# x-IMU3-SA-GPS.net
KiCad netlist of a schematic drawn in Altium Designer
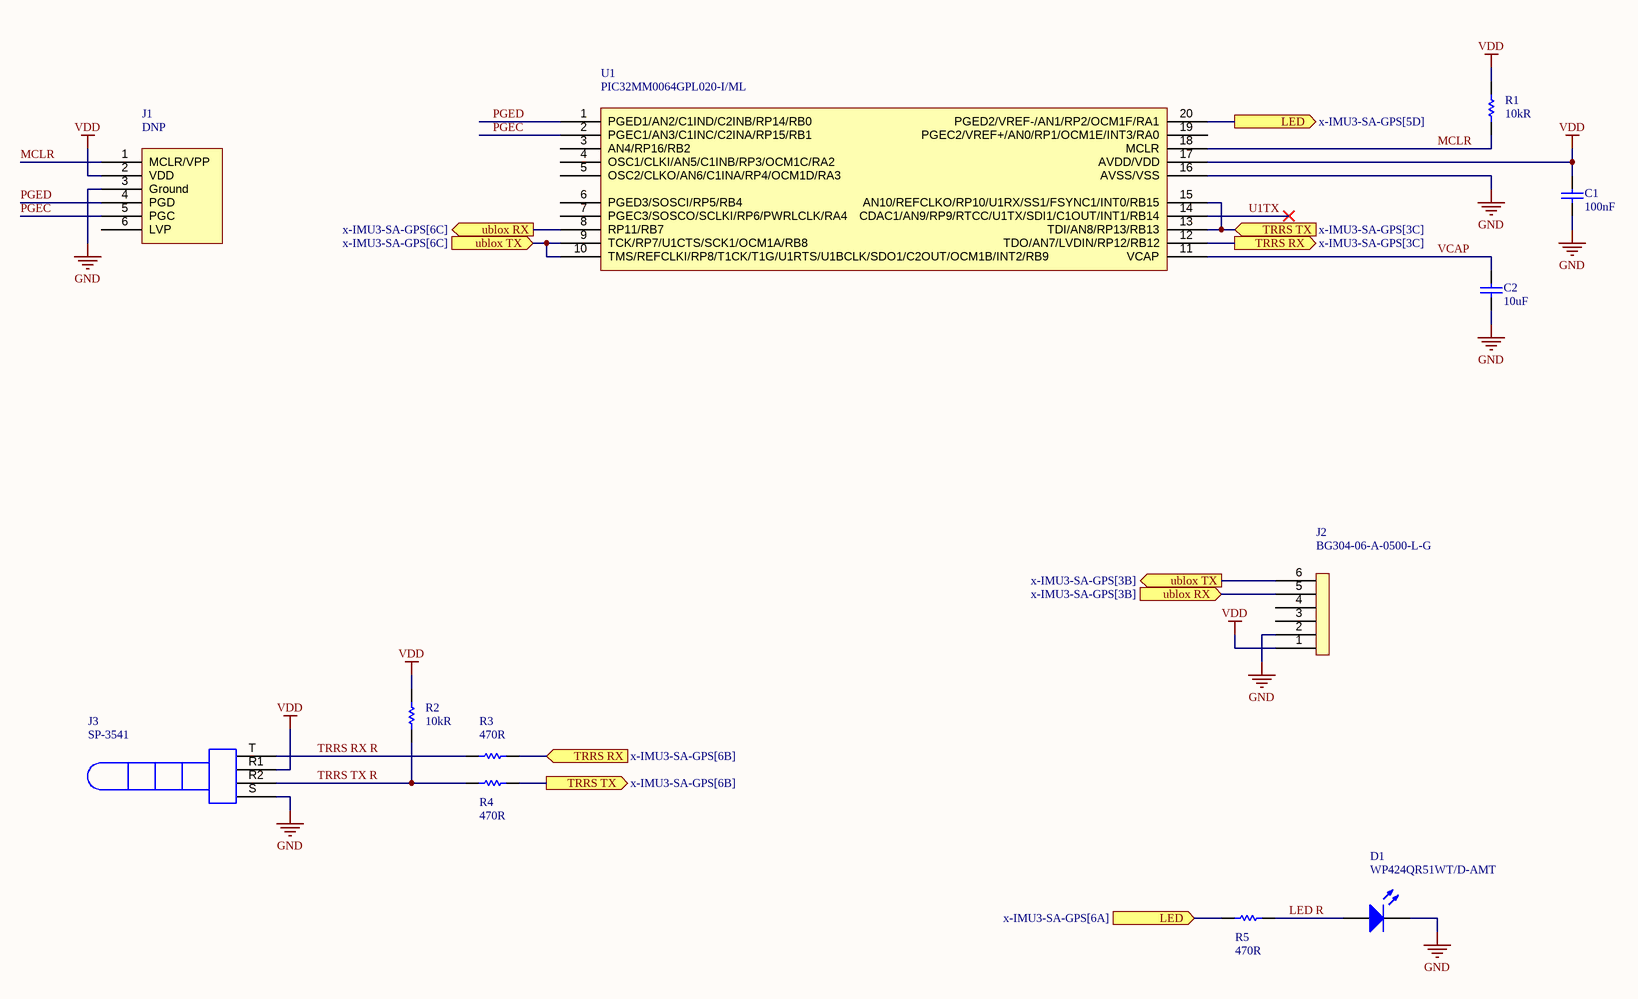
[diagram p0: x-IMU3-SA-GPS.SchDoc]

(export (version "E")
  (design (tool "Eeschema 10.0.6"))
  (components
    (comp (ref "C1") (value "100nF") (footprint "Capacitor 0402") (libsource (lib "x-io") (part "Capacitor")))
    (comp (ref "C2") (value "10uF") (footprint "Capacitor 0402") (libsource (lib "x-io") (part "Capacitor")))
    (comp (ref "D1") (value "WP424QR51WT/D-AMT") (footprint "LED 3mm") (libsource (lib "x-io") (part "LED")))
    (comp (ref "J1")
      (value "DNP")
      (footprint "Tag Connect No Legs")
      (libsource (lib "x-io") (part "MPLAB ICSP"))
    )
    (comp (ref "J2")
      (value "BG304-06-A-0500-L-G")
      (footprint "BG304-06-A-0500-L-G")
      (libsource (lib "x-io") (part "BG304-06-A-0500-L-G"))
    )
    (comp (ref "J3") (value "SP-3541") (footprint "SP-3541") (libsource (lib "x-io") (part "SP-3541")))
    (comp (ref "R1") (value "10kR") (footprint "Resistor 0402") (libsource (lib "x-io") (part "Resistor")))
    (comp (ref "R2") (value "10kR") (footprint "Resistor 0402") (libsource (lib "x-io") (part "Resistor")))
    (comp (ref "R3") (value "470R") (footprint "Resistor 0402") (libsource (lib "x-io") (part "Resistor")))
    (comp (ref "R4") (value "470R") (footprint "Resistor 0402") (libsource (lib "x-io") (part "Resistor")))
    (comp (ref "R5") (value "470R") (footprint "Resistor 0402") (libsource (lib "x-io") (part "Resistor")))
    (comp (ref "U1")
      (value "PIC32MM0064GPL020-I/ML")
      (footprint "QFN-20")
      (libsource (lib "x-io") (part "PIC32MM0064GPL020-I/ML"))
    )
  )
  (nets
    (net (code "1") (name "/LED") (class "Default")
      (node (ref "R5") (pin "2") (pinfunction "2_2") (pintype "passive"))
      (node (ref "U1") (pin "20") (pinfunction "PGED2/VREF-/AN1/RP2/OCM1F/RA1_20") (pintype "passive"))
    )
    (net (code "2") (name "/LED R") (class "Default")
      (node (ref "D1") (pin "A") (pinfunction "A_A") (pintype "passive"))
      (node (ref "R5") (pin "1") (pinfunction "1_1") (pintype "passive"))
    )
    (net (code "3") (name "/MCLR") (class "Default")
      (node (ref "J1") (pin "1") (pinfunction "MCLR/VPP_1") (pintype "passive"))
      (node (ref "R1") (pin "1") (pinfunction "1_1") (pintype "passive"))
      (node (ref "U1") (pin "18") (pinfunction "MCLR_18") (pintype "passive"))
    )
    (net (code "4") (name "/PGEC") (class "Default")
      (node (ref "J1") (pin "5") (pinfunction "PGC_5") (pintype "passive"))
      (node (ref "U1") (pin "2") (pinfunction "PGEC1/AN3/C1INC/C2INA/RP15/RB1_2") (pintype "passive"))
    )
    (net (code "5") (name "/PGED") (class "Default")
      (node (ref "J1") (pin "4") (pinfunction "PGD_4") (pintype "passive"))
      (node (ref "U1") (pin "1") (pinfunction "PGED1/AN2/C1IND/C2INB/RP14/RB0_1") (pintype "passive"))
    )
    (net (code "6") (name "/TRRS RX") (class "Default")
      (node (ref "R3") (pin "1") (pinfunction "1_1") (pintype "passive"))
      (node (ref "U1") (pin "12") (pinfunction "TDO/AN7/LVDIN/RP12/RB12_12") (pintype "passive"))
    )
    (net (code "7") (name "/TRRS RX R") (class "Default")
      (node (ref "J3") (pin "T") (pinfunction "T_T") (pintype "passive"))
      (node (ref "R3") (pin "2") (pinfunction "2_2") (pintype "passive"))
    )
    (net (code "8") (name "/TRRS TX") (class "Default")
      (node (ref "R4") (pin "1") (pinfunction "1_1") (pintype "passive"))
      (node (ref "U1") (pin "13") (pinfunction "TDI/AN8/RP13/RB13_13") (pintype "passive"))
      (node (ref "U1") (pin "15") (pinfunction "AN10/REFCLKO/RP10/U1RX/SS1/FSYNC1/INT0/RB15_15") (pintype "passive"))
    )
    (net (code "9") (name "/TRRS TX R") (class "Default")
      (node (ref "J3") (pin "R2") (pinfunction "R2_R2") (pintype "passive"))
      (node (ref "R2") (pin "1") (pinfunction "1_1") (pintype "passive"))
      (node (ref "R4") (pin "2") (pinfunction "2_2") (pintype "passive"))
    )
    (net (code "10") (name "/U1TX") (class "Default")
      (node (ref "U1") (pin "14") (pinfunction "CDAC1/AN9/RP9/RTCC/U1TX/SDI1/C1OUT/INT1/RB14_14") (pintype "passive+no_connect"))
    )
    (net (code "11") (name "/VCAP") (class "Default")
      (node (ref "C2") (pin "2") (pinfunction "2_2") (pintype "passive"))
      (node (ref "U1") (pin "11") (pinfunction "VCAP_11") (pintype "passive"))
    )
    (net (code "12") (name "/ublox RX") (class "Default")
      (node (ref "J2") (pin "5") (pinfunction "5_5") (pintype "passive"))
      (node (ref "U1") (pin "8") (pinfunction "RP11/RB7_8") (pintype "passive"))
    )
    (net (code "13") (name "/ublox TX") (class "Default")
      (node (ref "J2") (pin "6") (pinfunction "6_6") (pintype "passive"))
      (node (ref "U1") (pin "10") (pinfunction "TMS/REFCLKI/RP8/T1CK/T1G/U1RTS/U1BCLK/SDO1/C2OUT/OCM1B/INT2/RB9_10") (pintype "passive"))
      (node (ref "U1") (pin "9") (pinfunction "TCK/RP7/U1CTS/SCK1/OCM1A/RB8_9") (pintype "passive"))
    )
    (net (code "14") (name "GND") (class "Default")
      (node (ref "C1") (pin "1") (pinfunction "1_1") (pintype "passive"))
      (node (ref "C2") (pin "1") (pinfunction "1_1") (pintype "passive"))
      (node (ref "D1") (pin "K") (pinfunction "K_K") (pintype "passive"))
      (node (ref "J1") (pin "3") (pinfunction "Ground_3") (pintype "passive"))
      (node (ref "J2") (pin "2") (pinfunction "2_2") (pintype "passive"))
      (node (ref "J3") (pin "S") (pinfunction "S_S") (pintype "passive"))
      (node (ref "U1") (pin "16") (pinfunction "AVSS/VSS_16") (pintype "passive"))
    )
    (net (code "15") (name "VDD") (class "Default")
      (node (ref "C1") (pin "2") (pinfunction "2_2") (pintype "passive"))
      (node (ref "J1") (pin "2") (pinfunction "VDD_2") (pintype "passive"))
      (node (ref "J2") (pin "1") (pinfunction "1_1") (pintype "passive"))
      (node (ref "J3") (pin "R1") (pinfunction "R1_R1") (pintype "passive"))
      (node (ref "R1") (pin "2") (pinfunction "2_2") (pintype "passive"))
      (node (ref "R2") (pin "2") (pinfunction "2_2") (pintype "passive"))
      (node (ref "U1") (pin "17") (pinfunction "AVDD/VDD_17") (pintype "passive"))
    )
    (net (code "16") (name "unconnected-(J1-LVP-Pad6)") (class "Default")
      (node (ref "J1") (pin "6") (pinfunction "LVP_6") (pintype "passive"))
    )
    (net (code "17") (name "unconnected-(J2-Pad3)") (class "Default")
      (node (ref "J2") (pin "3") (pinfunction "3_3") (pintype "passive"))
    )
    (net (code "18") (name "unconnected-(J2-Pad4)") (class "Default")
      (node (ref "J2") (pin "4") (pinfunction "4_4") (pintype "passive"))
    )
    (net (code "19") (name "unconnected-(U1-AN4{slash}RP16{slash}RB2-Pad3)") (class "Default")
      (node (ref "U1") (pin "3") (pinfunction "AN4/RP16/RB2_3") (pintype "passive"))
    )
    (net (code "20") (name "unconnected-(U1-OSC1{slash}CLKI{slash}AN5{slash}C1INB{slash}RP3{slash}OCM1C{slash}RA2-Pad4)") (class "Default")
      (node (ref "U1") (pin "4") (pinfunction "OSC1/CLKI/AN5/C1INB/RP3/OCM1C/RA2_4") (pintype "passive"))
    )
    (net (code "21") (name "unconnected-(U1-OSC2{slash}CLKO{slash}AN6{slash}C1INA{slash}RP4{slash}OCM1D{slash}RA3-Pad5)") (class "Default")
      (node (ref "U1") (pin "5") (pinfunction "OSC2/CLKO/AN6/C1INA/RP4/OCM1D/RA3_5") (pintype "passive"))
    )
    (net (code "22") (name "unconnected-(U1-PGEC2{slash}VREF+{slash}AN0{slash}RP1{slash}OCM1E{slash}INT3{slash}RA0-Pad19)") (class "Default")
      (node (ref "U1") (pin "19") (pinfunction "PGEC2/VREF+/AN0/RP1/OCM1E/INT3/RA0_19") (pintype "passive"))
    )
    (net (code "23") (name "unconnected-(U1-PGEC3{slash}SOSCO{slash}SCLKI{slash}RP6{slash}PWRLCLK{slash}RA4-Pad7)") (class "Default")
      (node (ref "U1") (pin "7") (pinfunction "PGEC3/SOSCO/SCLKI/RP6/PWRLCLK/RA4_7") (pintype "passive"))
    )
    (net (code "24") (name "unconnected-(U1-PGED3{slash}SOSCI{slash}RP5{slash}RB4-Pad6)") (class "Default")
      (node (ref "U1") (pin "6") (pinfunction "PGED3/SOSCI/RP5/RB4_6") (pintype "passive"))
    )
  )
)
